# main.net
KiCad netlist of a schematic drawn in EAGLE
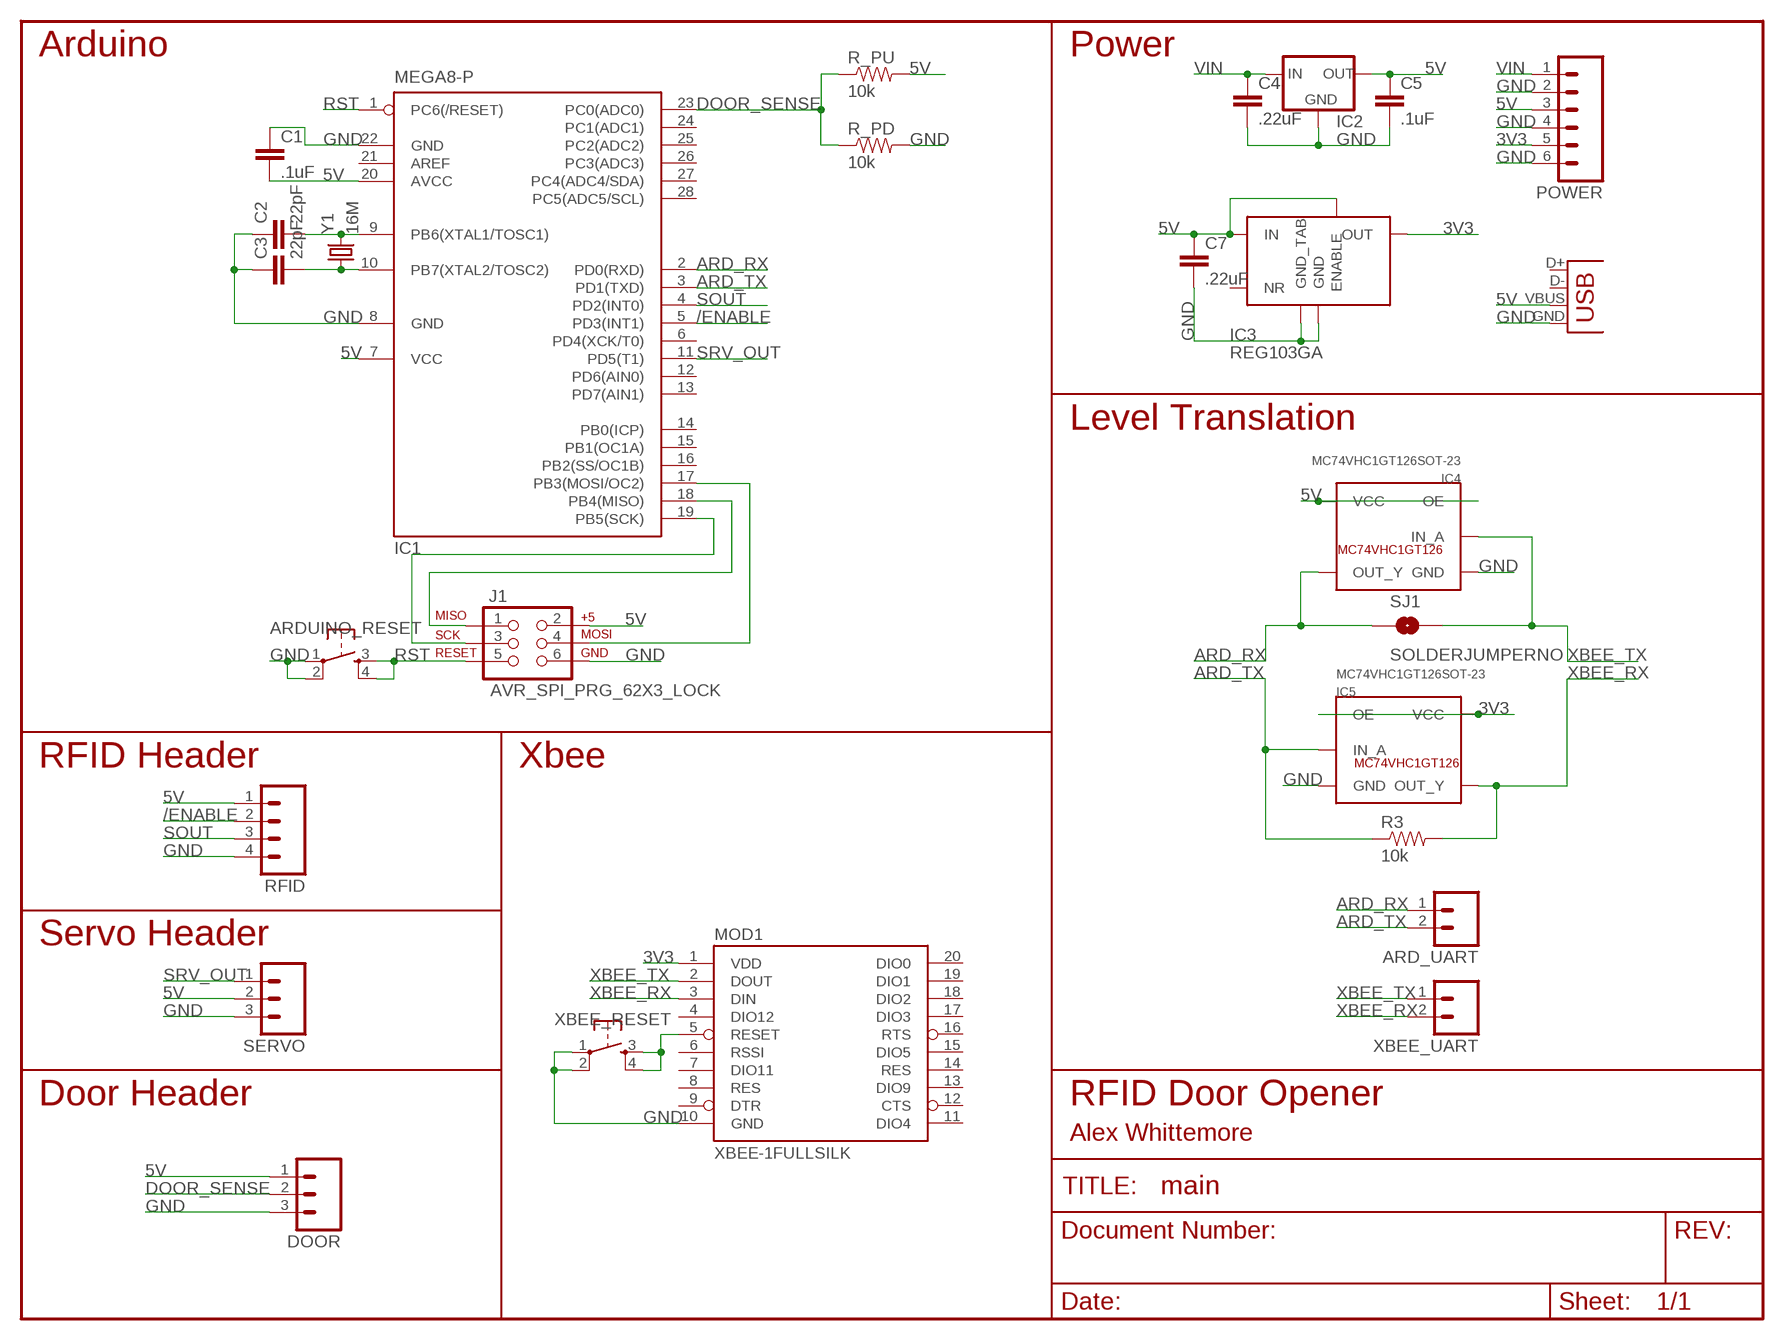
[diagram p0: schematic, sheet 1]

(export (version "E")
  (design (tool "Eeschema 10.0.6"))
  (components
    (comp (ref "ARDUINO_RESET")
      (value "TAC_SWITCHPTH")
      (footprint "eagle-import:TACTILE-PTH")
      (libsource (lib "eagle-import") (part "TAC_SWITCHPTH"))
    )
    (comp (ref "ARD_UART")
      (value "M02LOCK_LONGPADS")
      (footprint "eagle-import:1X02_LOCK_LONGPADS")
      (libsource (lib "eagle-import") (part "M02LOCK_LONGPADS"))
    )
    (comp (ref "C1")
      (value ".1uF")
      (footprint "eagle-import:0805")
      (libsource (lib "eagle-import") (part "CAP0805"))
    )
    (comp (ref "C2")
      (value "22pF")
      (footprint "eagle-import:0805")
      (libsource (lib "eagle-import") (part "CAP0805"))
    )
    (comp (ref "C3")
      (value "22pF")
      (footprint "eagle-import:0805")
      (libsource (lib "eagle-import") (part "CAP0805"))
    )
    (comp (ref "C4")
      (value ".22uF")
      (footprint "eagle-import:0805")
      (libsource (lib "eagle-import") (part "CAP0805"))
    )
    (comp (ref "C5")
      (value ".1uF")
      (footprint "eagle-import:0805")
      (libsource (lib "eagle-import") (part "CAP0805"))
    )
    (comp (ref "C7")
      (value ".22uF")
      (footprint "eagle-import:0805")
      (libsource (lib "eagle-import") (part "CAP0805"))
    )
    (comp (ref "DOOR")
      (value "M03LOCK")
      (footprint "eagle-import:1X03_LOCK")
      (libsource (lib "eagle-import") (part "M03LOCK"))
    )
    (comp (ref "IC1")
      (value "MEGA8-P")
      (footprint "eagle-import:DIL28-3")
      (libsource (lib "eagle-import") (part "MEGA8-P"))
    )
    (comp (ref "IC2")
      (value "V_REG_78XX-TO-220")
      (footprint "eagle-import:TO-220-ALT")
      (libsource (lib "eagle-import") (part "V_REG_78XX-TO-220"))
    )
    (comp (ref "IC3")
      (value "REG103GA")
      (footprint "eagle-import:SOT223-5")
      (libsource (lib "eagle-import") (part "REG103GA"))
    )
    (comp (ref "IC4")
      (value "MC74VHC1GT126SOT-23")
      (footprint "eagle-import:SOT23-5L")
      (libsource (lib "eagle-import") (part "MC74VHC1GT126SOT-23"))
    )
    (comp (ref "IC5")
      (value "MC74VHC1GT126SOT-23")
      (footprint "eagle-import:SOT23-5L")
      (libsource (lib "eagle-import") (part "MC74VHC1GT126SOT-23"))
    )
    (comp (ref "J1")
      (value "AVR_SPI_PRG_62X3_LOCK")
      (footprint "eagle-import:2X3_LOCK")
      (libsource (lib "eagle-import") (part "AVR_SPI_PRG_62X3_LOCK"))
    )
    (comp (ref "MOD1")
      (value "XBEE-1FULLSILK")
      (footprint "eagle-import:XBEE")
      (libsource (lib "eagle-import") (part "XBEE-1FULLSILK"))
    )
    (comp (ref "POWER")
      (value "M06LOCK")
      (footprint "eagle-import:1X06_LOCK")
      (libsource (lib "eagle-import") (part "M06LOCK"))
    )
    (comp (ref "R3")
      (value "10k")
      (footprint "eagle-import:0805")
      (libsource (lib "eagle-import") (part "RESISTOR0805-RES"))
    )
    (comp (ref "RFID")
      (value "M04LOCK_LONGPADS")
      (footprint "eagle-import:1X04_LOCK_LONGPADS")
      (libsource (lib "eagle-import") (part "M04LOCK_LONGPADS"))
    )
    (comp (ref "R_PD")
      (value "10k")
      (footprint "eagle-import:0805")
      (libsource (lib "eagle-import") (part "RESISTOR0805-RES"))
    )
    (comp (ref "R_PU")
      (value "10k")
      (footprint "eagle-import:0805")
      (libsource (lib "eagle-import") (part "RESISTOR0805-RES"))
    )
    (comp (ref "SERVO")
      (value "M03LOCK")
      (footprint "eagle-import:1X03_LOCK")
      (libsource (lib "eagle-import") (part "M03LOCK"))
    )
    (comp (ref "SJ1")
      (value "SOLDERJUMPERNO")
      (footprint "eagle-import:SJ_2S-NO")
      (libsource (lib "eagle-import") (part "SOLDERJUMPERNO"))
    )
    (comp (ref "X1")
      (value "USB-SMD-NS")
      (footprint "eagle-import:USB-MINIB-NOSTOP")
      (libsource (lib "eagle-import") (part "USB-SMD-NS"))
    )
    (comp (ref "XBEE_RESET")
      (value "TAC_SWITCHPTH")
      (footprint "eagle-import:TACTILE-PTH")
      (libsource (lib "eagle-import") (part "TAC_SWITCHPTH"))
    )
    (comp (ref "XBEE_UART")
      (value "M02LOCK_LONGPADS")
      (footprint "eagle-import:1X02_LOCK_LONGPADS")
      (libsource (lib "eagle-import") (part "M02LOCK_LONGPADS"))
    )
    (comp (ref "Y1")
      (value "16M")
      (footprint "eagle-import:HC49UP")
      (libsource (lib "eagle-import") (part "CRYSTALSMD"))
    )
  )
  (nets
    (net (code "1") (name "/3V3") (class "Default")
      (node (ref "IC3") (pin "2") (pinfunction "OUT_2") (pintype "bidirectional"))
      (node (ref "IC5") (pin "1") (pinfunction "OE_1") (pintype "bidirectional"))
      (node (ref "IC5") (pin "5") (pinfunction "VCC_5") (pintype "bidirectional"))
      (node (ref "MOD1") (pin "1") (pinfunction "VDD_1") (pintype "power_in"))
      (node (ref "POWER") (pin "5") (pinfunction "5_5") (pintype "passive"))
    )
    (net (code "2") (name "/5V") (class "Default")
      (node (ref "C1") (pin "2") (pinfunction "2_2") (pintype "passive"))
      (node (ref "C5") (pin "1") (pinfunction "1_1") (pintype "passive"))
      (node (ref "C7") (pin "1") (pinfunction "1_1") (pintype "passive"))
      (node (ref "DOOR") (pin "1") (pinfunction "1_1") (pintype "passive"))
      (node (ref "IC1") (pin "20") (pinfunction "AVCC_20") (pintype "power_in"))
      (node (ref "IC1") (pin "7") (pinfunction "VCC_7") (pintype "power_in"))
      (node (ref "IC2") (pin "OUT") (pinfunction "OUT_OUT") (pintype "output"))
      (node (ref "IC3") (pin "1") (pinfunction "IN_1") (pintype "bidirectional"))
      (node (ref "IC3") (pin "5") (pinfunction "ENABLE_5") (pintype "bidirectional"))
      (node (ref "IC4") (pin "1") (pinfunction "OE_1") (pintype "bidirectional"))
      (node (ref "IC4") (pin "5") (pinfunction "VCC_5") (pintype "bidirectional"))
      (node (ref "J1") (pin "2") (pinfunction "2_2") (pintype "passive"))
      (node (ref "POWER") (pin "3") (pinfunction "3_3") (pintype "passive"))
      (node (ref "RFID") (pin "1") (pinfunction "1_1") (pintype "passive"))
      (node (ref "R_PU") (pin "2") (pinfunction "2_2") (pintype "passive"))
      (node (ref "SERVO") (pin "2") (pinfunction "2_2") (pintype "passive"))
      (node (ref "X1") (pin "VBUS") (pinfunction "VBUS_VBUS") (pintype "bidirectional"))
    )
    (net (code "3") (name "/ARD_RX") (class "Default")
      (node (ref "ARD_UART") (pin "1") (pinfunction "1_1") (pintype "passive"))
      (node (ref "IC1") (pin "2") (pinfunction "PD0(RXD)_2") (pintype "bidirectional"))
      (node (ref "IC4") (pin "4") (pinfunction "OUT_Y_4") (pintype "bidirectional"))
      (node (ref "SJ1") (pin "1") (pinfunction "1_1") (pintype "passive"))
    )
    (net (code "4") (name "/ARD_TX") (class "Default")
      (node (ref "ARD_UART") (pin "2") (pinfunction "2_2") (pintype "passive"))
      (node (ref "IC1") (pin "3") (pinfunction "PD1(TXD)_3") (pintype "bidirectional"))
      (node (ref "IC5") (pin "2") (pinfunction "IN_A_2") (pintype "bidirectional"))
      (node (ref "R3") (pin "1") (pinfunction "1_1") (pintype "passive"))
    )
    (net (code "5") (name "/DOOR_SENSE") (class "Default")
      (node (ref "DOOR") (pin "2") (pinfunction "2_2") (pintype "passive"))
      (node (ref "IC1") (pin "23") (pinfunction "PC0(ADC0)_23") (pintype "bidirectional"))
      (node (ref "R_PD") (pin "1") (pinfunction "1_1") (pintype "passive"))
      (node (ref "R_PU") (pin "1") (pinfunction "1_1") (pintype "passive"))
    )
    (net (code "6") (name "/GND") (class "Default")
      (node (ref "ARDUINO_RESET") (pin "1") (pinfunction "1_1") (pintype "passive"))
      (node (ref "ARDUINO_RESET") (pin "2") (pinfunction "2_2") (pintype "passive"))
      (node (ref "C1") (pin "1") (pinfunction "1_1") (pintype "passive"))
      (node (ref "C2") (pin "1") (pinfunction "1_1") (pintype "passive"))
      (node (ref "C3") (pin "1") (pinfunction "1_1") (pintype "passive"))
      (node (ref "C4") (pin "2") (pinfunction "2_2") (pintype "passive"))
      (node (ref "C5") (pin "2") (pinfunction "2_2") (pintype "passive"))
      (node (ref "C7") (pin "2") (pinfunction "2_2") (pintype "passive"))
      (node (ref "DOOR") (pin "3") (pinfunction "3_3") (pintype "passive"))
      (node (ref "IC1") (pin "22") (pinfunction "GND_22") (pintype "power_in"))
      (node (ref "IC1") (pin "8") (pinfunction "GND_8") (pintype "power_in"))
      (node (ref "IC2") (pin "GND") (pinfunction "GND_GND") (pintype "input"))
      (node (ref "IC3") (pin "3") (pinfunction "GND_3") (pintype "bidirectional"))
      (node (ref "IC3") (pin "TAB") (pinfunction "GND_TAB_TAB") (pintype "bidirectional"))
      (node (ref "IC4") (pin "3") (pinfunction "GND_3") (pintype "bidirectional"))
      (node (ref "IC5") (pin "3") (pinfunction "GND_3") (pintype "bidirectional"))
      (node (ref "J1") (pin "6") (pinfunction "6_6") (pintype "passive"))
      (node (ref "MOD1") (pin "10") (pinfunction "GND_10") (pintype "power_in"))
      (node (ref "POWER") (pin "2") (pinfunction "2_2") (pintype "passive"))
      (node (ref "POWER") (pin "4") (pinfunction "4_4") (pintype "passive"))
      (node (ref "POWER") (pin "6") (pinfunction "6_6") (pintype "passive"))
      (node (ref "RFID") (pin "4") (pinfunction "4_4") (pintype "passive"))
      (node (ref "R_PD") (pin "2") (pinfunction "2_2") (pintype "passive"))
      (node (ref "SERVO") (pin "3") (pinfunction "3_3") (pintype "passive"))
      (node (ref "X1") (pin "GND") (pinfunction "GND_GND") (pintype "bidirectional"))
      (node (ref "XBEE_RESET") (pin "1") (pinfunction "1_1") (pintype "passive"))
      (node (ref "XBEE_RESET") (pin "2") (pinfunction "2_2") (pintype "passive"))
    )
    (net (code "7") (name "/RST") (class "Default")
      (node (ref "ARDUINO_RESET") (pin "3") (pinfunction "3_3") (pintype "passive"))
      (node (ref "ARDUINO_RESET") (pin "4") (pinfunction "4_4") (pintype "passive"))
      (node (ref "IC1") (pin "1") (pinfunction "PC6(/RESET)_1") (pintype "bidirectional"))
      (node (ref "J1") (pin "5") (pinfunction "5_5") (pintype "passive"))
    )
    (net (code "8") (name "/SOUT") (class "Default")
      (node (ref "IC1") (pin "4") (pinfunction "PD2(INT0)_4") (pintype "bidirectional"))
      (node (ref "RFID") (pin "3") (pinfunction "3_3") (pintype "passive"))
    )
    (net (code "9") (name "/SRV_OUT") (class "Default")
      (node (ref "IC1") (pin "11") (pinfunction "PD5(T1)_11") (pintype "bidirectional"))
      (node (ref "SERVO") (pin "1") (pinfunction "1_1") (pintype "passive"))
    )
    (net (code "10") (name "/VIN") (class "Default")
      (node (ref "C4") (pin "1") (pinfunction "1_1") (pintype "passive"))
      (node (ref "IC2") (pin "IN") (pinfunction "IN_IN") (pintype "input"))
      (node (ref "POWER") (pin "1") (pinfunction "1_1") (pintype "passive"))
    )
    (net (code "11") (name "/XBEE_RX") (class "Default")
      (node (ref "IC5") (pin "4") (pinfunction "OUT_Y_4") (pintype "bidirectional"))
      (node (ref "MOD1") (pin "3") (pinfunction "DIN_3") (pintype "input"))
      (node (ref "R3") (pin "2") (pinfunction "2_2") (pintype "passive"))
      (node (ref "XBEE_UART") (pin "2") (pinfunction "2_2") (pintype "passive"))
    )
    (net (code "12") (name "/XBEE_TX") (class "Default")
      (node (ref "IC4") (pin "2") (pinfunction "IN_A_2") (pintype "bidirectional"))
      (node (ref "MOD1") (pin "2") (pinfunction "DOUT_2") (pintype "output"))
      (node (ref "SJ1") (pin "2") (pinfunction "2_2") (pintype "passive"))
      (node (ref "XBEE_UART") (pin "1") (pinfunction "1_1") (pintype "passive"))
    )
    (net (code "13") (name "/{slash}ENABLE") (class "Default")
      (node (ref "IC1") (pin "5") (pinfunction "PD3(INT1)_5") (pintype "bidirectional"))
      (node (ref "RFID") (pin "2") (pinfunction "2_2") (pintype "passive"))
    )
    (net (code "14") (name "Net-(IC1-PB3(MOSI{slash}OC2))") (class "Default")
      (node (ref "IC1") (pin "17") (pinfunction "PB3(MOSI/OC2)_17") (pintype "bidirectional"))
      (node (ref "J1") (pin "4") (pinfunction "4_4") (pintype "passive"))
    )
    (net (code "15") (name "Net-(IC1-PB4(MISO))") (class "Default")
      (node (ref "IC1") (pin "18") (pinfunction "PB4(MISO)_18") (pintype "bidirectional"))
      (node (ref "J1") (pin "1") (pinfunction "1_1") (pintype "passive"))
    )
    (net (code "16") (name "Net-(IC1-PB5(SCK))") (class "Default")
      (node (ref "IC1") (pin "19") (pinfunction "PB5(SCK)_19") (pintype "bidirectional"))
      (node (ref "J1") (pin "3") (pinfunction "3_3") (pintype "passive"))
    )
    (net (code "17") (name "Net-(IC1-PB6(XTAL1{slash}TOSC1))") (class "Default")
      (node (ref "C2") (pin "2") (pinfunction "2_2") (pintype "passive"))
      (node (ref "IC1") (pin "9") (pinfunction "PB6(XTAL1/TOSC1)_9") (pintype "bidirectional"))
      (node (ref "Y1") (pin "2") (pinfunction "2_2") (pintype "passive"))
    )
    (net (code "18") (name "Net-(IC1-PB7(XTAL2{slash}TOSC2))") (class "Default")
      (node (ref "C3") (pin "2") (pinfunction "2_2") (pintype "passive"))
      (node (ref "IC1") (pin "10") (pinfunction "PB7(XTAL2/TOSC2)_10") (pintype "bidirectional"))
      (node (ref "Y1") (pin "1") (pinfunction "1_1") (pintype "passive"))
    )
    (net (code "19") (name "Net-(MOD1-RESET)") (class "Default")
      (node (ref "MOD1") (pin "5") (pinfunction "RESET_5") (pintype "input"))
      (node (ref "XBEE_RESET") (pin "3") (pinfunction "3_3") (pintype "passive"))
      (node (ref "XBEE_RESET") (pin "4") (pinfunction "4_4") (pintype "passive"))
    )
    (net (code "20") (name "unconnected-(IC1-AREF-Pad21)") (class "Default")
      (node (ref "IC1") (pin "21") (pinfunction "AREF_21") (pintype "passive"))
    )
    (net (code "21") (name "unconnected-(IC1-PB0(ICP)-Pad14)") (class "Default")
      (node (ref "IC1") (pin "14") (pinfunction "PB0(ICP)_14") (pintype "bidirectional"))
    )
    (net (code "22") (name "unconnected-(IC1-PB1(OC1A)-Pad15)") (class "Default")
      (node (ref "IC1") (pin "15") (pinfunction "PB1(OC1A)_15") (pintype "bidirectional"))
    )
    (net (code "23") (name "unconnected-(IC1-PB2(SS{slash}OC1B)-Pad16)") (class "Default")
      (node (ref "IC1") (pin "16") (pinfunction "PB2(SS/OC1B)_16") (pintype "bidirectional"))
    )
    (net (code "24") (name "unconnected-(IC1-PC1(ADC1)-Pad24)") (class "Default")
      (node (ref "IC1") (pin "24") (pinfunction "PC1(ADC1)_24") (pintype "bidirectional"))
    )
    (net (code "25") (name "unconnected-(IC1-PC2(ADC2)-Pad25)") (class "Default")
      (node (ref "IC1") (pin "25") (pinfunction "PC2(ADC2)_25") (pintype "bidirectional"))
    )
    (net (code "26") (name "unconnected-(IC1-PC3(ADC3)-Pad26)") (class "Default")
      (node (ref "IC1") (pin "26") (pinfunction "PC3(ADC3)_26") (pintype "bidirectional"))
    )
    (net (code "27") (name "unconnected-(IC1-PC4(ADC4{slash}SDA)-Pad27)") (class "Default")
      (node (ref "IC1") (pin "27") (pinfunction "PC4(ADC4/SDA)_27") (pintype "bidirectional"))
    )
    (net (code "28") (name "unconnected-(IC1-PC5(ADC5{slash}SCL)-Pad28)") (class "Default")
      (node (ref "IC1") (pin "28") (pinfunction "PC5(ADC5/SCL)_28") (pintype "bidirectional"))
    )
    (net (code "29") (name "unconnected-(IC1-PD4(XCK{slash}T0)-Pad6)") (class "Default")
      (node (ref "IC1") (pin "6") (pinfunction "PD4(XCK/T0)_6") (pintype "bidirectional"))
    )
    (net (code "30") (name "unconnected-(IC1-PD6(AIN0)-Pad12)") (class "Default")
      (node (ref "IC1") (pin "12") (pinfunction "PD6(AIN0)_12") (pintype "bidirectional"))
    )
    (net (code "31") (name "unconnected-(IC1-PD7(AIN1)-Pad13)") (class "Default")
      (node (ref "IC1") (pin "13") (pinfunction "PD7(AIN1)_13") (pintype "bidirectional"))
    )
    (net (code "32") (name "unconnected-(IC3-NR-Pad4)") (class "Default")
      (node (ref "IC3") (pin "4") (pinfunction "NR_4") (pintype "bidirectional"))
    )
    (net (code "33") (name "unconnected-(MOD1-CTS-Pad12)") (class "Default")
      (node (ref "MOD1") (pin "12") (pinfunction "CTS_12") (pintype "output"))
    )
    (net (code "34") (name "unconnected-(MOD1-DIO0-Pad20)") (class "Default")
      (node (ref "MOD1") (pin "20") (pinfunction "DIO0_20") (pintype "bidirectional"))
    )
    (net (code "35") (name "unconnected-(MOD1-DIO1-Pad19)") (class "Default")
      (node (ref "MOD1") (pin "19") (pinfunction "DIO1_19") (pintype "bidirectional"))
    )
    (net (code "36") (name "unconnected-(MOD1-DIO2-Pad18)") (class "Default")
      (node (ref "MOD1") (pin "18") (pinfunction "DIO2_18") (pintype "bidirectional"))
    )
    (net (code "37") (name "unconnected-(MOD1-DIO3-Pad17)") (class "Default")
      (node (ref "MOD1") (pin "17") (pinfunction "DIO3_17") (pintype "bidirectional"))
    )
    (net (code "38") (name "unconnected-(MOD1-DIO4-Pad11)") (class "Default")
      (node (ref "MOD1") (pin "11") (pinfunction "DIO4_11") (pintype "bidirectional"))
    )
    (net (code "39") (name "unconnected-(MOD1-DIO5-Pad15)") (class "Default")
      (node (ref "MOD1") (pin "15") (pinfunction "DIO5_15") (pintype "bidirectional"))
    )
    (net (code "40") (name "unconnected-(MOD1-DIO9-Pad13)") (class "Default")
      (node (ref "MOD1") (pin "13") (pinfunction "DIO9_13") (pintype "bidirectional"))
    )
    (net (code "41") (name "unconnected-(MOD1-DIO11-Pad7)") (class "Default")
      (node (ref "MOD1") (pin "7") (pinfunction "DIO11_7") (pintype "bidirectional"))
    )
    (net (code "42") (name "unconnected-(MOD1-DIO12-Pad4)") (class "Default")
      (node (ref "MOD1") (pin "4") (pinfunction "DIO12_4") (pintype "bidirectional"))
    )
    (net (code "43") (name "unconnected-(MOD1-DTR-Pad9)") (class "Default")
      (node (ref "MOD1") (pin "9") (pinfunction "DTR_9") (pintype "bidirectional"))
    )
    (net (code "44") (name "unconnected-(MOD1-RES-Pad8)") (class "Default")
      (node (ref "MOD1") (pin "8") (pinfunction "RES_8") (pintype "bidirectional"))
    )
    (net (code "45") (name "unconnected-(MOD1-RES-Pad14)") (class "Default")
      (node (ref "MOD1") (pin "14") (pinfunction "RES_14") (pintype "bidirectional"))
    )
    (net (code "46") (name "unconnected-(MOD1-RSSI-Pad6)") (class "Default")
      (node (ref "MOD1") (pin "6") (pinfunction "RSSI_6") (pintype "bidirectional"))
    )
    (net (code "47") (name "unconnected-(MOD1-RTS-Pad16)") (class "Default")
      (node (ref "MOD1") (pin "16") (pinfunction "RTS_16") (pintype "input"))
    )
    (net (code "48") (name "unconnected-(X1-PadD+)") (class "Default")
      (node (ref "X1") (pin "D+") (pinfunction "D+_D+") (pintype "bidirectional"))
    )
    (net (code "49") (name "unconnected-(X1-PadD-)") (class "Default")
      (node (ref "X1") (pin "D-") (pinfunction "D-_D-") (pintype "bidirectional"))
    )
  )
)
